# RP2040.net
KiCad netlist of a schematic drawn in Altium Designer
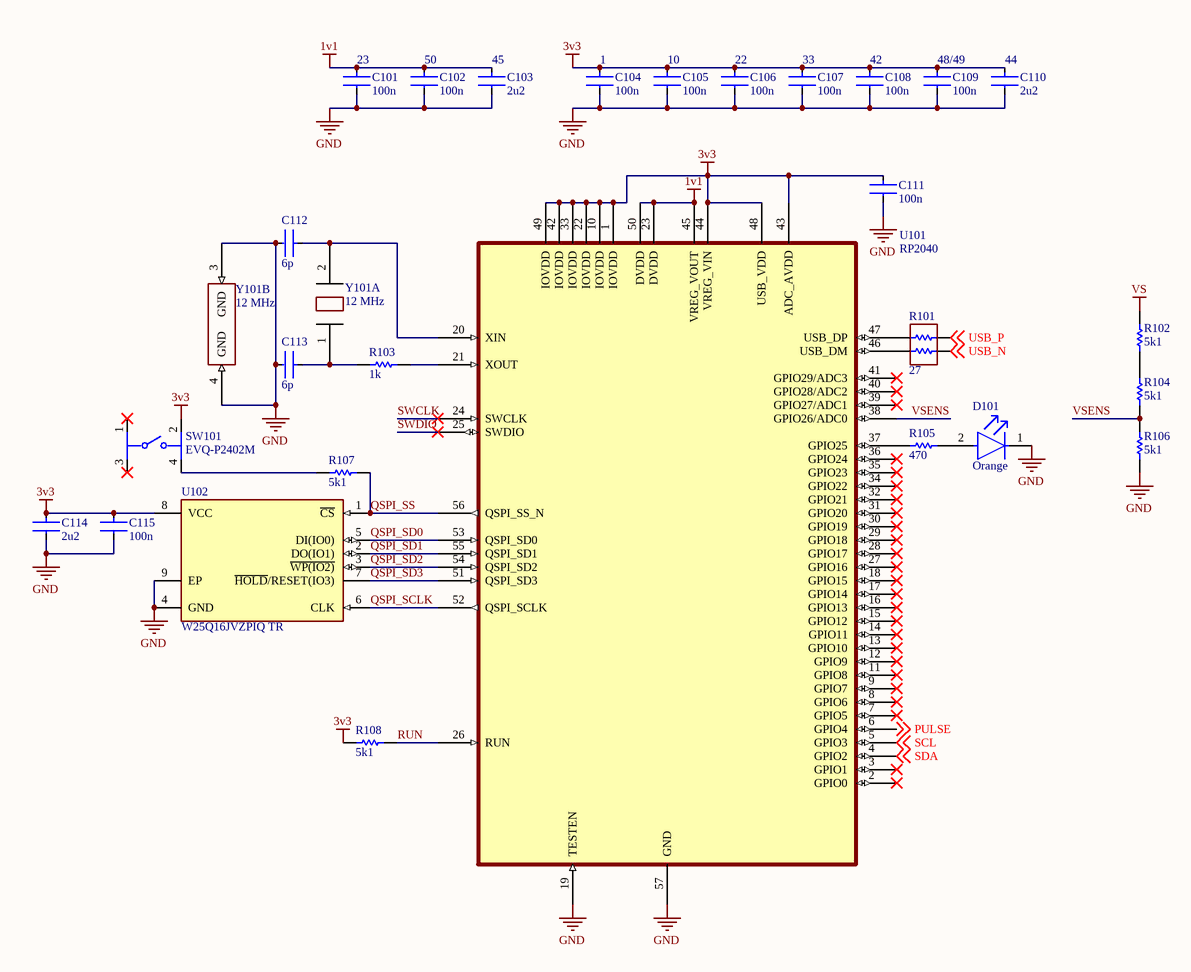
[diagram p0: RP2040.SchDoc]

(export (version "E")
  (design (tool "Eeschema 10.0.6"))
  (components
    (comp (ref "C101")
      (value "100n")
      (footprint "FP-GCM155-0_05-MFG")
      (description "Ceramic Capacitor for Automotive 100nF ±10% 50VDC X7R 0402 Paper T/R")
      (fields (field (name "TOLERANCE") "10%"))
      (libsource (lib "Main") (part "GCM155R71H104KE02J"))
    )
    (comp (ref "C102")
      (value "100n")
      (footprint "FP-GCM155-0_05-MFG")
      (description "Ceramic Capacitor for Automotive 100nF ±10% 50VDC X7R 0402 Paper T/R")
      (fields (field (name "TOLERANCE") "10%"))
      (libsource (lib "Main") (part "GCM155R71H104KE02J"))
    )
    (comp (ref "C103")
      (value "2u2")
      (footprint "CAPC1608X10N")
      (description "Multilayer Ceramic Capacitors MLCC - SMD/SMT 0603 50Vdc 2.2uF X5R 20%")
      (libsource (lib "Main") (part "GRT188R61H225ME13D"))
    )
    (comp (ref "C104")
      (value "100n")
      (footprint "FP-GCM155-0_05-MFG")
      (description "Ceramic Capacitor for Automotive 100nF ±10% 50VDC X7R 0402 Paper T/R")
      (fields (field (name "TOLERANCE") "10%"))
      (libsource (lib "Main") (part "GCM155R71H104KE02J"))
    )
    (comp (ref "C105")
      (value "100n")
      (footprint "FP-GCM155-0_05-MFG")
      (description "Ceramic Capacitor for Automotive 100nF ±10% 50VDC X7R 0402 Paper T/R")
      (fields (field (name "TOLERANCE") "10%"))
      (libsource (lib "Main") (part "GCM155R71H104KE02J"))
    )
    (comp (ref "C106")
      (value "100n")
      (footprint "FP-GCM155-0_05-MFG")
      (description "Ceramic Capacitor for Automotive 100nF ±10% 50VDC X7R 0402 Paper T/R")
      (fields (field (name "TOLERANCE") "10%"))
      (libsource (lib "Main") (part "GCM155R71H104KE02J"))
    )
    (comp (ref "C107")
      (value "100n")
      (footprint "FP-GCM155-0_05-MFG")
      (description "Ceramic Capacitor for Automotive 100nF ±10% 50VDC X7R 0402 Paper T/R")
      (fields (field (name "TOLERANCE") "10%"))
      (libsource (lib "Main") (part "GCM155R71H104KE02J"))
    )
    (comp (ref "C108")
      (value "100n")
      (footprint "FP-GCM155-0_05-MFG")
      (description "Ceramic Capacitor for Automotive 100nF ±10% 50VDC X7R 0402 Paper T/R")
      (fields (field (name "TOLERANCE") "10%"))
      (libsource (lib "Main") (part "GCM155R71H104KE02J"))
    )
    (comp (ref "C109")
      (value "100n")
      (footprint "FP-GCM155-0_05-MFG")
      (description "Ceramic Capacitor for Automotive 100nF ±10% 50VDC X7R 0402 Paper T/R")
      (fields (field (name "TOLERANCE") "10%"))
      (libsource (lib "Main") (part "GCM155R71H104KE02J"))
    )
    (comp (ref "C110")
      (value "2u2")
      (footprint "CAPC1608X10N")
      (description "Multilayer Ceramic Capacitors MLCC - SMD/SMT 0603 50Vdc 2.2uF X5R 20%")
      (libsource (lib "Main") (part "GRT188R61H225ME13D"))
    )
    (comp (ref "C111")
      (value "100n")
      (footprint "FP-GCM155-0_05-MFG")
      (description "Ceramic Capacitor for Automotive 100nF ±10% 50VDC X7R 0402 Paper T/R")
      (fields (field (name "TOLERANCE") "10%"))
      (libsource (lib "Main") (part "GCM155R71H104KE02J"))
    )
    (comp (ref "C112")
      (value "6p")
      (footprint "FP-GCQ155-0_05-MFG")
      (description "High Q Ceramic Capacitor for Automotive 6pF ±0.1pF 50VDC C0G 0402 Paper T/R")
      (libsource (lib "Main") (part "GCQ1555C1H6R0BB01D"))
    )
    (comp (ref "C113")
      (value "6p")
      (footprint "FP-GCQ155-0_05-MFG")
      (description "High Q Ceramic Capacitor for Automotive 6pF ±0.1pF 50VDC C0G 0402 Paper T/R")
      (libsource (lib "Main") (part "GCQ1555C1H6R0BB01D"))
    )
    (comp (ref "C114")
      (value "2u2")
      (footprint "CAPC1608X10N")
      (description "Multilayer Ceramic Capacitors MLCC - SMD/SMT 0603 50Vdc 2.2uF X5R 20%")
      (libsource (lib "Main") (part "GRT188R61H225ME13D"))
    )
    (comp (ref "C115")
      (value "100n")
      (footprint "FP-GCM155-0_05-MFG")
      (description "Ceramic Capacitor for Automotive 100nF ±10% 50VDC X7R 0402 Paper T/R")
      (fields (field (name "TOLERANCE") "10%"))
      (libsource (lib "Main") (part "GCM155R71H104KE02J"))
    )
    (comp (ref "D101")
      (value "Orange")
      (footprint "FP-SML-P1-MFG")
      (description "LED ORANGE CLEAR 1006 SMD")
      (fields
        (field (name "MANUFACTURER PART NUMBER") "SML-P11DTT86R")
        (field (name "OCTOPART") "https://octopart.com/sml-p11dtt86r-rohm-34112313")
      )
      (libsource (lib "Main") (part "SML-P11DTT86R"))
    )
    (comp (ref "R101")
      (value "27")
      (footprint "CAC-65P100X100-4L")
      (libsource (lib "Main") (part "EXB-24V270JX"))
    )
    (comp (ref "R102")
      (value "5k1")
      (footprint "RESC1005X04N")
      (fields (field (name "MANUFACTURER") "Panasonic") (field (name "PART NUMBER") "ERJ2RKF27R0X"))
      (libsource (lib "Main") (part "ERJ-U02J512X"))
    )
    (comp (ref "R103")
      (value "1k")
      (footprint "RESC1005X04N")
      (fields (field (name "MANUFACTURER") "Panasonic") (field (name "PART NUMBER") "ERJ-2GEJ102X"))
      (libsource (lib "Main") (part "ERJ-2GEJ102X"))
    )
    (comp (ref "R104")
      (value "5k1")
      (footprint "RESC1005X04N")
      (fields (field (name "MANUFACTURER") "Panasonic") (field (name "PART NUMBER") "ERJ2RKF27R0X"))
      (libsource (lib "Main") (part "ERJ-U02J512X"))
    )
    (comp (ref "R105")
      (value "470")
      (footprint "RESC1005X04N")
      (fields (field (name "MANUFACTURER") "Panasonic") (field (name "PART NUMBER") "ERJ2RKF27R0X"))
      (libsource (lib "Main") (part "ERJ-U02J471X"))
    )
    (comp (ref "R106")
      (value "5k1")
      (footprint "RESC1005X04N")
      (fields (field (name "MANUFACTURER") "Panasonic") (field (name "PART NUMBER") "ERJ2RKF27R0X"))
      (libsource (lib "Main") (part "ERJ-U02J512X"))
    )
    (comp (ref "R107")
      (value "5k1")
      (footprint "RESC1005X04N")
      (fields (field (name "MANUFACTURER") "Panasonic") (field (name "PART NUMBER") "ERJ2RKF27R0X"))
      (libsource (lib "Main") (part "ERJ-U02J512X"))
    )
    (comp (ref "R108")
      (value "5k1")
      (footprint "RESC1005X04N")
      (fields (field (name "MANUFACTURER") "Panasonic") (field (name "PART NUMBER") "ERJ2RKF27R0X"))
      (libsource (lib "Main") (part "ERJ-U02J512X"))
    )
    (comp (ref "SW101")
      (value "EVQ-P2402M")
      (footprint "EVQ-P2402M")
      (libsource (lib "Main") (part "EVQ-P2402M"))
    )
    (comp (ref "U101")
      (value "RP2040")
      (footprint "QFN40P700X700X90_HS-57N")
      (libsource (lib "Main") (part "RP2040"))
    )
    (comp (ref "U102")
      (value "W25Q16JVZPIQ TR")
      (footprint "WSON-8")
      (description "IC FLASH 16M SPI 133MHZ 8WSON")
      (libsource (lib "Main") (part "W25Q16JVZPIQ TR"))
    )
    (comp (ref "Y101")
      (value "12 MHz")
      (footprint "XTAL_ABRACON_ABM10")
      (libsource (lib "Main") (part "ABM10-166-12.000MHZ-T3"))
    )
  )
  (nets
    (net (code "1") (name "/QSPI_SCLK") (class "Default")
      (node (ref "U101") (pin "52") (pinfunction "QSPI_SCLK_52") (pintype "output"))
      (node (ref "U102") (pin "6") (pinfunction "CLK_6") (pintype "input"))
    )
    (net (code "2") (name "/QSPI_SD0") (class "Default")
      (node (ref "U101") (pin "53") (pinfunction "QSPI_SD0_53") (pintype "input"))
      (node (ref "U102") (pin "5") (pinfunction "DI(IO0)_5") (pintype "bidirectional"))
    )
    (net (code "3") (name "/QSPI_SD1") (class "Default")
      (node (ref "U101") (pin "55") (pinfunction "QSPI_SD1_55") (pintype "input"))
      (node (ref "U102") (pin "2") (pinfunction "DO(IO1)_2") (pintype "bidirectional"))
    )
    (net (code "4") (name "/QSPI_SD2") (class "Default")
      (node (ref "U101") (pin "54") (pinfunction "QSPI_SD2_54") (pintype "input"))
      (node (ref "U102") (pin "3") (pinfunction "~{WP(IO2)}_3") (pintype "bidirectional"))
    )
    (net (code "5") (name "/QSPI_SD3") (class "Default")
      (node (ref "U101") (pin "51") (pinfunction "QSPI_SD3_51") (pintype "input"))
      (node (ref "U102") (pin "7") (pinfunction "~{HOLD}/RESET(IO3)_7") (pintype "passive"))
    )
    (net (code "6") (name "/QSPI_SS") (class "Default")
      (node (ref "R107") (pin "2") (pinfunction "2_2") (pintype "passive"))
      (node (ref "U101") (pin "56") (pinfunction "QSPI_SS_N_56") (pintype "output"))
      (node (ref "U102") (pin "1") (pinfunction "~{CS}_1") (pintype "input"))
    )
    (net (code "7") (name "/RUN") (class "Default")
      (node (ref "R108") (pin "2") (pinfunction "2_2") (pintype "passive"))
      (node (ref "U101") (pin "26") (pinfunction "RUN_26") (pintype "input"))
    )
    (net (code "8") (name "/SWCLK") (class "Default")
      (node (ref "U101") (pin "24") (pinfunction "SWCLK_24") (pintype "input+no_connect"))
    )
    (net (code "9") (name "/SWDIO") (class "Default")
      (node (ref "U101") (pin "25") (pinfunction "SWDIO_25") (pintype "bidirectional+no_connect"))
    )
    (net (code "10") (name "/VSENS") (class "Default")
      (node (ref "R104") (pin "1") (pinfunction "1_1") (pintype "passive"))
      (node (ref "R106") (pin "2") (pinfunction "2_2") (pintype "passive"))
      (node (ref "U101") (pin "38") (pinfunction "GPIO26/ADC0_38") (pintype "bidirectional"))
    )
    (net (code "11") (name "1v1") (class "Default")
      (node (ref "C101") (pin "1") (pinfunction "1_1") (pintype "passive"))
      (node (ref "C102") (pin "1") (pinfunction "1_1") (pintype "passive"))
      (node (ref "C103") (pin "1") (pinfunction "1_1") (pintype "passive"))
      (node (ref "U101") (pin "23") (pinfunction "DVDD_23") (pintype "power_in"))
      (node (ref "U101") (pin "45") (pinfunction "VREG_VOUT_45") (pintype "power_in"))
      (node (ref "U101") (pin "50") (pinfunction "DVDD_50") (pintype "power_in"))
    )
    (net (code "12") (name "3v3") (class "Default")
      (node (ref "C104") (pin "1") (pinfunction "1_1") (pintype "passive"))
      (node (ref "C105") (pin "1") (pinfunction "1_1") (pintype "passive"))
      (node (ref "C106") (pin "1") (pinfunction "1_1") (pintype "passive"))
      (node (ref "C107") (pin "1") (pinfunction "1_1") (pintype "passive"))
      (node (ref "C108") (pin "1") (pinfunction "1_1") (pintype "passive"))
      (node (ref "C109") (pin "1") (pinfunction "1_1") (pintype "passive"))
      (node (ref "C110") (pin "1") (pinfunction "1_1") (pintype "passive"))
      (node (ref "C111") (pin "1") (pinfunction "1_1") (pintype "passive"))
      (node (ref "C114") (pin "1") (pinfunction "1_1") (pintype "passive"))
      (node (ref "C115") (pin "1") (pinfunction "1_1") (pintype "passive"))
      (node (ref "R108") (pin "1") (pinfunction "1_1") (pintype "passive"))
      (node (ref "SW101") (pin "2") (pinfunction "2_2") (pintype "passive"))
      (node (ref "U101") (pin "1") (pinfunction "IOVDD_1") (pintype "power_in"))
      (node (ref "U101") (pin "10") (pinfunction "IOVDD_10") (pintype "power_in"))
      (node (ref "U101") (pin "22") (pinfunction "IOVDD_22") (pintype "power_in"))
      (node (ref "U101") (pin "33") (pinfunction "IOVDD_33") (pintype "power_in"))
      (node (ref "U101") (pin "42") (pinfunction "IOVDD_42") (pintype "power_in"))
      (node (ref "U101") (pin "43") (pinfunction "ADC_AVDD_43") (pintype "power_in"))
      (node (ref "U101") (pin "44") (pinfunction "VREG_VIN_44") (pintype "power_in"))
      (node (ref "U101") (pin "48") (pinfunction "USB_VDD_48") (pintype "power_in"))
      (node (ref "U101") (pin "49") (pinfunction "IOVDD_49") (pintype "power_in"))
      (node (ref "U102") (pin "8") (pinfunction "VCC_8") (pintype "power_in"))
    )
    (net (code "13") (name "GND") (class "Default")
      (node (ref "C101") (pin "2") (pinfunction "2_2") (pintype "passive"))
      (node (ref "C102") (pin "2") (pinfunction "2_2") (pintype "passive"))
      (node (ref "C103") (pin "2") (pinfunction "2_2") (pintype "passive"))
      (node (ref "C104") (pin "2") (pinfunction "2_2") (pintype "passive"))
      (node (ref "C105") (pin "2") (pinfunction "2_2") (pintype "passive"))
      (node (ref "C106") (pin "2") (pinfunction "2_2") (pintype "passive"))
      (node (ref "C107") (pin "2") (pinfunction "2_2") (pintype "passive"))
      (node (ref "C108") (pin "2") (pinfunction "2_2") (pintype "passive"))
      (node (ref "C109") (pin "2") (pinfunction "2_2") (pintype "passive"))
      (node (ref "C110") (pin "2") (pinfunction "2_2") (pintype "passive"))
      (node (ref "C111") (pin "2") (pinfunction "2_2") (pintype "passive"))
      (node (ref "C112") (pin "2") (pinfunction "2_2") (pintype "passive"))
      (node (ref "C113") (pin "2") (pinfunction "2_2") (pintype "passive"))
      (node (ref "C114") (pin "2") (pinfunction "2_2") (pintype "passive"))
      (node (ref "C115") (pin "2") (pinfunction "2_2") (pintype "passive"))
      (node (ref "D101") (pin "1") (pinfunction "C_1") (pintype "passive"))
      (node (ref "R106") (pin "1") (pinfunction "1_1") (pintype "passive"))
      (node (ref "U101") (pin "19") (pinfunction "TESTEN_19") (pintype "input"))
      (node (ref "U101") (pin "57") (pinfunction "GND_57") (pintype "power_in"))
      (node (ref "U102") (pin "4") (pinfunction "GND_4") (pintype "power_in"))
      (node (ref "U102") (pin "9") (pinfunction "EP_9") (pintype "passive"))
      (node (ref "Y101") (pin "3") (pinfunction "GND_3") (pintype "input"))
      (node (ref "Y101") (pin "4") (pinfunction "GND_4") (pintype "input"))
    )
    (net (code "14") (name "Net-(C113-Pad1)") (class "Default")
      (node (ref "C113") (pin "1") (pinfunction "1_1") (pintype "passive"))
      (node (ref "R103") (pin "1") (pinfunction "1_1") (pintype "passive"))
      (node (ref "Y101") (pin "1") (pintype "passive"))
    )
    (net (code "15") (name "Net-(D101-A)") (class "Default")
      (node (ref "D101") (pin "2") (pinfunction "A_2") (pintype "passive"))
      (node (ref "R105") (pin "2") (pinfunction "2_2") (pintype "passive"))
    )
    (net (code "16") (name "Net-(R102-Pad1)") (class "Default")
      (node (ref "R102") (pin "1") (pinfunction "1_1") (pintype "passive"))
      (node (ref "R104") (pin "2") (pinfunction "2_2") (pintype "passive"))
    )
    (net (code "17") (name "Net-(R107-Pad1)") (class "Default")
      (node (ref "R107") (pin "1") (pinfunction "1_1") (pintype "passive"))
      (node (ref "SW101") (pin "4") (pinfunction "4_4") (pintype "passive"))
    )
    (net (code "18") (name "Net-(U101-GPIO25)") (class "Default")
      (node (ref "R105") (pin "1") (pinfunction "1_1") (pintype "passive"))
      (node (ref "U101") (pin "37") (pinfunction "GPIO25_37") (pintype "bidirectional"))
    )
    (net (code "19") (name "Net-(U101-USB_DM)") (class "Default")
      (node (ref "R101") (pin "2") (pinfunction "2_2") (pintype "passive"))
      (node (ref "U101") (pin "46") (pinfunction "USB_DM_46") (pintype "bidirectional"))
    )
    (net (code "20") (name "Net-(U101-USB_DP)") (class "Default")
      (node (ref "R101") (pin "1") (pinfunction "1_1") (pintype "passive"))
      (node (ref "U101") (pin "47") (pinfunction "USB_DP_47") (pintype "bidirectional"))
    )
    (net (code "21") (name "Net-(U101-XIN)") (class "Default")
      (node (ref "C112") (pin "1") (pinfunction "1_1") (pintype "passive"))
      (node (ref "U101") (pin "20") (pinfunction "XIN_20") (pintype "input"))
      (node (ref "Y101") (pin "2") (pintype "passive"))
    )
    (net (code "22") (name "Net-(U101-XOUT)") (class "Default")
      (node (ref "R103") (pin "2") (pinfunction "2_2") (pintype "passive"))
      (node (ref "U101") (pin "21") (pinfunction "XOUT_21") (pintype "input"))
    )
    (net (code "23") (name "PULSE") (class "Default")
      (node (ref "U101") (pin "6") (pinfunction "GPIO4_6") (pintype "bidirectional"))
    )
    (net (code "24") (name "SCL") (class "Default")
      (node (ref "U101") (pin "5") (pinfunction "GPIO3_5") (pintype "bidirectional"))
    )
    (net (code "25") (name "SDA") (class "Default")
      (node (ref "U101") (pin "4") (pinfunction "GPIO2_4") (pintype "bidirectional"))
    )
    (net (code "26") (name "USB_N") (class "Default")
      (node (ref "R101") (pin "3") (pinfunction "3_3") (pintype "passive"))
    )
    (net (code "27") (name "USB_P") (class "Default")
      (node (ref "R101") (pin "4") (pinfunction "4_4") (pintype "passive"))
    )
    (net (code "28") (name "VS") (class "Default")
      (node (ref "R102") (pin "2") (pinfunction "2_2") (pintype "passive"))
    )
    (net (code "29") (name "unconnected-(SW101-Pad1)") (class "Default")
      (node (ref "SW101") (pin "1") (pinfunction "1_1") (pintype "passive+no_connect"))
    )
    (net (code "30") (name "unconnected-(SW101-Pad3)") (class "Default")
      (node (ref "SW101") (pin "3") (pinfunction "3_3") (pintype "passive+no_connect"))
    )
    (net (code "31") (name "unconnected-(U101-GPIO0-Pad2)") (class "Default")
      (node (ref "U101") (pin "2") (pinfunction "GPIO0_2") (pintype "bidirectional+no_connect"))
    )
    (net (code "32") (name "unconnected-(U101-GPIO1-Pad3)") (class "Default")
      (node (ref "U101") (pin "3") (pinfunction "GPIO1_3") (pintype "bidirectional+no_connect"))
    )
    (net (code "33") (name "unconnected-(U101-GPIO5-Pad7)") (class "Default")
      (node (ref "U101") (pin "7") (pinfunction "GPIO5_7") (pintype "bidirectional+no_connect"))
    )
    (net (code "34") (name "unconnected-(U101-GPIO6-Pad8)") (class "Default")
      (node (ref "U101") (pin "8") (pinfunction "GPIO6_8") (pintype "bidirectional+no_connect"))
    )
    (net (code "35") (name "unconnected-(U101-GPIO7-Pad9)") (class "Default")
      (node (ref "U101") (pin "9") (pinfunction "GPIO7_9") (pintype "bidirectional+no_connect"))
    )
    (net (code "36") (name "unconnected-(U101-GPIO8-Pad11)") (class "Default")
      (node (ref "U101") (pin "11") (pinfunction "GPIO8_11") (pintype "bidirectional+no_connect"))
    )
    (net (code "37") (name "unconnected-(U101-GPIO9-Pad12)") (class "Default")
      (node (ref "U101") (pin "12") (pinfunction "GPIO9_12") (pintype "bidirectional+no_connect"))
    )
    (net (code "38") (name "unconnected-(U101-GPIO10-Pad13)") (class "Default")
      (node (ref "U101") (pin "13") (pinfunction "GPIO10_13") (pintype "bidirectional+no_connect"))
    )
    (net (code "39") (name "unconnected-(U101-GPIO11-Pad14)") (class "Default")
      (node (ref "U101") (pin "14") (pinfunction "GPIO11_14") (pintype "bidirectional+no_connect"))
    )
    (net (code "40") (name "unconnected-(U101-GPIO12-Pad15)") (class "Default")
      (node (ref "U101") (pin "15") (pinfunction "GPIO12_15") (pintype "bidirectional+no_connect"))
    )
    (net (code "41") (name "unconnected-(U101-GPIO13-Pad16)") (class "Default")
      (node (ref "U101") (pin "16") (pinfunction "GPIO13_16") (pintype "bidirectional+no_connect"))
    )
    (net (code "42") (name "unconnected-(U101-GPIO14-Pad17)") (class "Default")
      (node (ref "U101") (pin "17") (pinfunction "GPIO14_17") (pintype "bidirectional+no_connect"))
    )
    (net (code "43") (name "unconnected-(U101-GPIO15-Pad18)") (class "Default")
      (node (ref "U101") (pin "18") (pinfunction "GPIO15_18") (pintype "bidirectional+no_connect"))
    )
    (net (code "44") (name "unconnected-(U101-GPIO16-Pad27)") (class "Default")
      (node (ref "U101") (pin "27") (pinfunction "GPIO16_27") (pintype "bidirectional+no_connect"))
    )
    (net (code "45") (name "unconnected-(U101-GPIO17-Pad28)") (class "Default")
      (node (ref "U101") (pin "28") (pinfunction "GPIO17_28") (pintype "bidirectional+no_connect"))
    )
    (net (code "46") (name "unconnected-(U101-GPIO18-Pad29)") (class "Default")
      (node (ref "U101") (pin "29") (pinfunction "GPIO18_29") (pintype "bidirectional+no_connect"))
    )
    (net (code "47") (name "unconnected-(U101-GPIO19-Pad30)") (class "Default")
      (node (ref "U101") (pin "30") (pinfunction "GPIO19_30") (pintype "bidirectional+no_connect"))
    )
    (net (code "48") (name "unconnected-(U101-GPIO20-Pad31)") (class "Default")
      (node (ref "U101") (pin "31") (pinfunction "GPIO20_31") (pintype "bidirectional+no_connect"))
    )
    (net (code "49") (name "unconnected-(U101-GPIO21-Pad32)") (class "Default")
      (node (ref "U101") (pin "32") (pinfunction "GPIO21_32") (pintype "bidirectional+no_connect"))
    )
    (net (code "50") (name "unconnected-(U101-GPIO22-Pad34)") (class "Default")
      (node (ref "U101") (pin "34") (pinfunction "GPIO22_34") (pintype "bidirectional+no_connect"))
    )
    (net (code "51") (name "unconnected-(U101-GPIO23-Pad35)") (class "Default")
      (node (ref "U101") (pin "35") (pinfunction "GPIO23_35") (pintype "bidirectional+no_connect"))
    )
    (net (code "52") (name "unconnected-(U101-GPIO24-Pad36)") (class "Default")
      (node (ref "U101") (pin "36") (pinfunction "GPIO24_36") (pintype "bidirectional+no_connect"))
    )
    (net (code "53") (name "unconnected-(U101-GPIO27{slash}ADC1-Pad39)") (class "Default")
      (node (ref "U101") (pin "39") (pinfunction "GPIO27/ADC1_39") (pintype "bidirectional+no_connect"))
    )
    (net (code "54") (name "unconnected-(U101-GPIO28{slash}ADC2-Pad40)") (class "Default")
      (node (ref "U101") (pin "40") (pinfunction "GPIO28/ADC2_40") (pintype "bidirectional+no_connect"))
    )
    (net (code "55") (name "unconnected-(U101-GPIO29{slash}ADC3-Pad41)") (class "Default")
      (node (ref "U101") (pin "41") (pinfunction "GPIO29/ADC3_41") (pintype "bidirectional+no_connect"))
    )
  )
)
